# ATTinyServo_v10.net
KiCad netlist of a schematic drawn in EAGLE
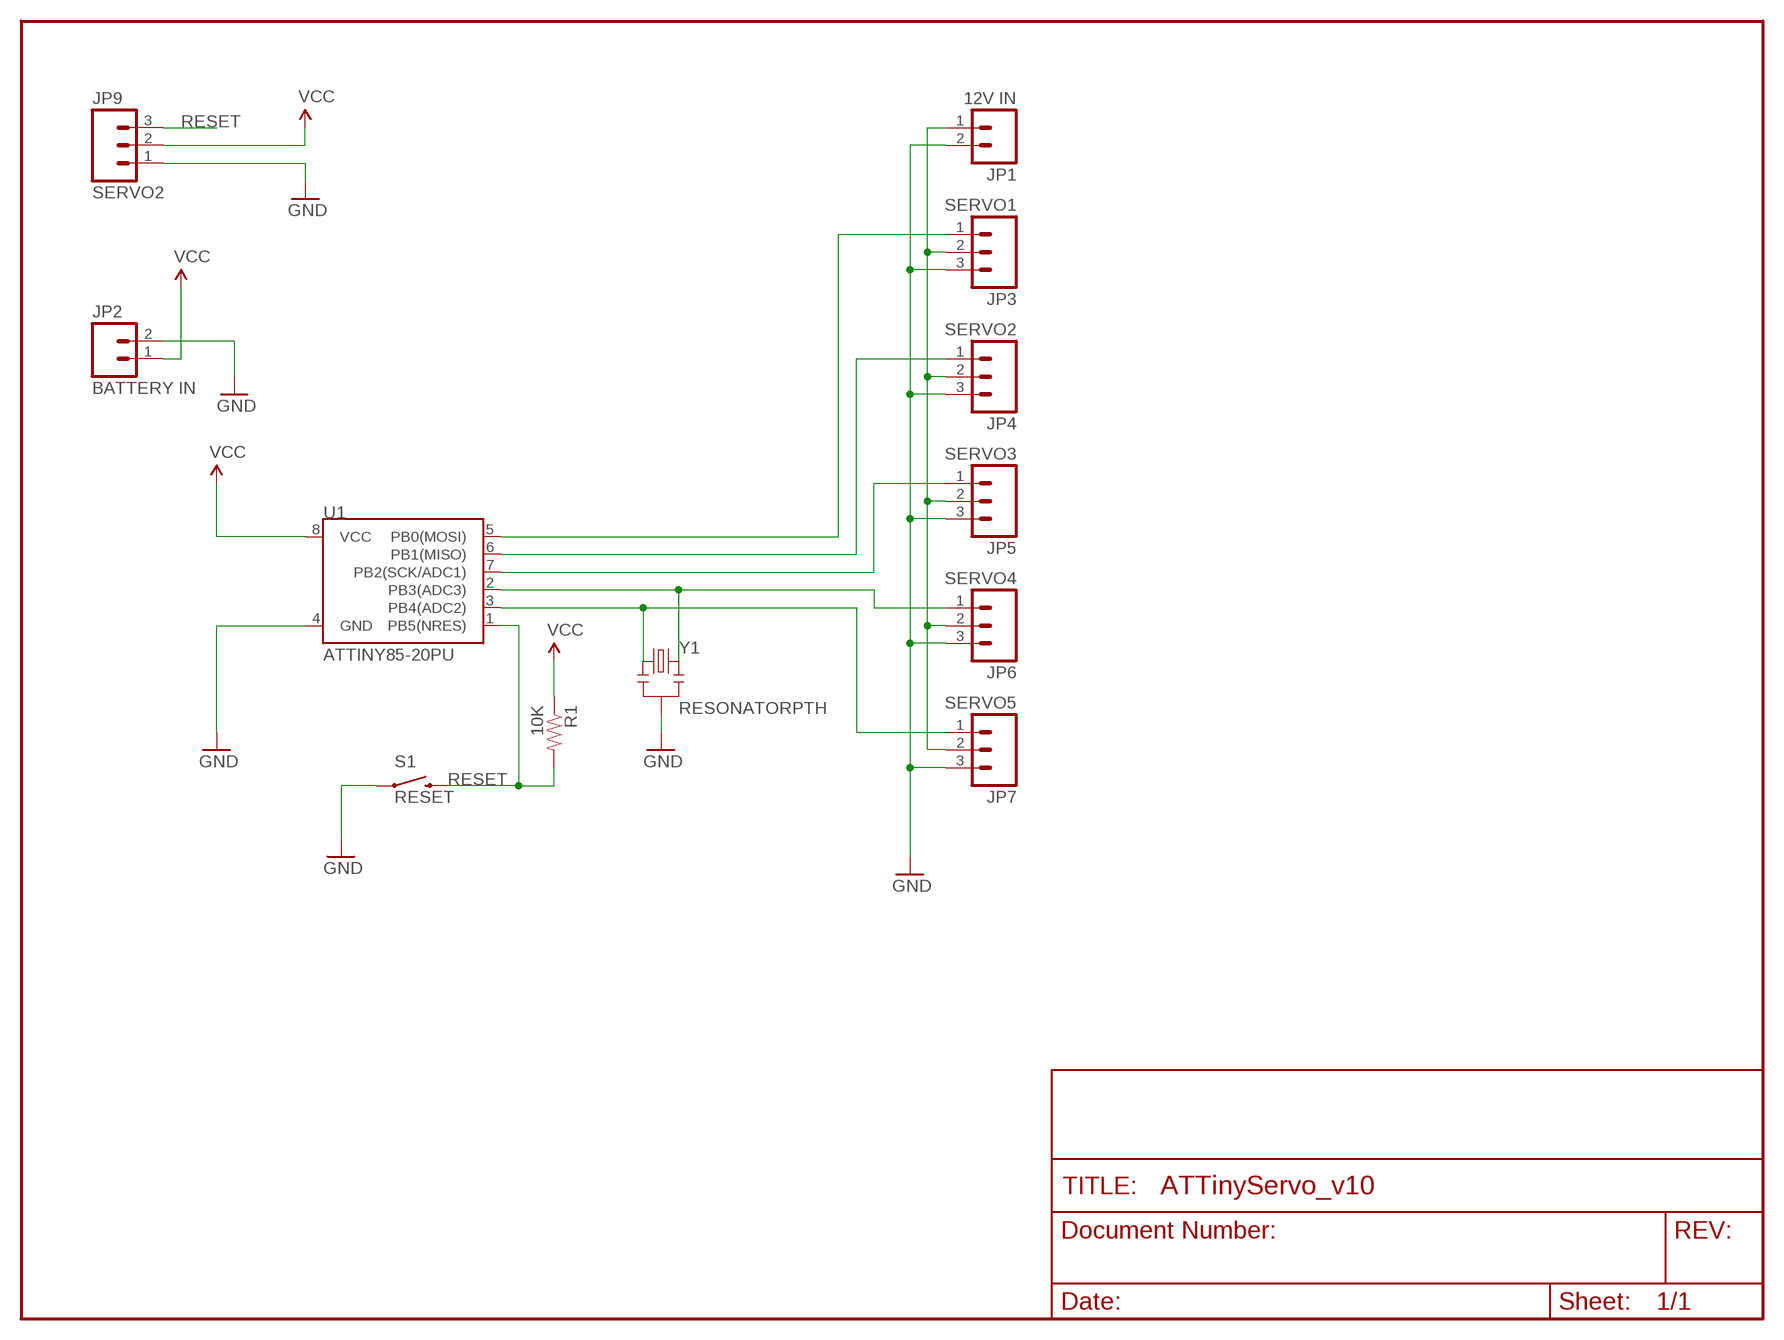
[diagram p0: schematic, sheet 1]

(export (version "E")
  (design (tool "Eeschema 10.0.6"))
  (components
    (comp (ref "JP1")
      (value "12V IN")
      (footprint "eagle-import:SCREWTERMINAL-3.5MM-2")
      (libsource (lib "eagle-import") (part "M023.5MM"))
    )
    (comp (ref "JP2")
      (value "BATTERY IN")
      (footprint "eagle-import:SCREWTERMINAL-3.5MM-2")
      (libsource (lib "eagle-import") (part "M023.5MM"))
    )
    (comp (ref "JP3")
      (value "SERVO1")
      (footprint "eagle-import:1X03")
      (libsource (lib "eagle-import") (part "M03PTH"))
    )
    (comp (ref "JP4")
      (value "SERVO2")
      (footprint "eagle-import:1X03")
      (libsource (lib "eagle-import") (part "M03PTH"))
    )
    (comp (ref "JP5")
      (value "SERVO3")
      (footprint "eagle-import:1X03")
      (libsource (lib "eagle-import") (part "M03PTH"))
    )
    (comp (ref "JP6")
      (value "SERVO4")
      (footprint "eagle-import:1X03")
      (libsource (lib "eagle-import") (part "M03PTH"))
    )
    (comp (ref "JP7")
      (value "SERVO5")
      (footprint "eagle-import:1X03")
      (libsource (lib "eagle-import") (part "M03PTH"))
    )
    (comp (ref "JP9")
      (value "SERVO2")
      (footprint "eagle-import:1X03")
      (libsource (lib "eagle-import") (part "M03PTH"))
    )
    (comp (ref "R1")
      (value "10K")
      (footprint "eagle-import:AXIAL-0.4")
      (libsource (lib "eagle-import") (part "RESISTORPTH-1/4W"))
    )
    (comp (ref "S1")
      (value "RESET")
      (footprint "eagle-import:TACTILE-PTH")
      (libsource (lib "eagle-import") (part "SWITCH-MOMENTARY-2PTH"))
    )
    (comp (ref "U1")
      (value "ATTINY85-20PU")
      (footprint "eagle-import:DIP08")
      (libsource (lib "eagle-import") (part "ATTINY45DIP8"))
    )
    (comp (ref "Y1")
      (value "RESONATORPTH")
      (footprint "eagle-import:RESONATOR-PTH")
      (libsource (lib "eagle-import") (part "RESONATORPTH"))
    )
  )
  (nets
    (net (code "1") (name "/RESET") (class "Default")
      (node (ref "JP9") (pin "3") (pinfunction "3_3") (pintype "passive"))
      (node (ref "R1") (pin "P$2") (pinfunction "2_P$2") (pintype "passive"))
      (node (ref "S1") (pin "3") (pinfunction "2_3") (pintype "passive"))
      (node (ref "U1") (pin "1") (pinfunction "PB5(NRES)_1") (pintype "bidirectional"))
    )
    (net (code "2") (name "GND") (class "Default")
      (node (ref "JP1") (pin "2") (pinfunction "2_2") (pintype "passive"))
      (node (ref "JP2") (pin "2") (pinfunction "2_2") (pintype "passive"))
      (node (ref "JP3") (pin "3") (pinfunction "3_3") (pintype "passive"))
      (node (ref "JP4") (pin "3") (pinfunction "3_3") (pintype "passive"))
      (node (ref "JP5") (pin "3") (pinfunction "3_3") (pintype "passive"))
      (node (ref "JP6") (pin "3") (pinfunction "3_3") (pintype "passive"))
      (node (ref "JP7") (pin "3") (pinfunction "3_3") (pintype "passive"))
      (node (ref "JP9") (pin "1") (pinfunction "1_1") (pintype "passive"))
      (node (ref "S1") (pin "1") (pinfunction "1_1") (pintype "passive"))
      (node (ref "U1") (pin "4") (pinfunction "GND_4") (pintype "bidirectional"))
      (node (ref "Y1") (pin "2") (pinfunction "2_2") (pintype "passive"))
    )
    (net (code "3") (name "Net-(JP1-Pad1)") (class "Default")
      (node (ref "JP1") (pin "1") (pinfunction "1_1") (pintype "passive"))
      (node (ref "JP3") (pin "2") (pinfunction "2_2") (pintype "passive"))
      (node (ref "JP4") (pin "2") (pinfunction "2_2") (pintype "passive"))
      (node (ref "JP5") (pin "2") (pinfunction "2_2") (pintype "passive"))
      (node (ref "JP6") (pin "2") (pinfunction "2_2") (pintype "passive"))
      (node (ref "JP7") (pin "2") (pinfunction "2_2") (pintype "passive"))
    )
    (net (code "4") (name "Net-(U1-PB0(MOSI))") (class "Default")
      (node (ref "JP3") (pin "1") (pinfunction "1_1") (pintype "passive"))
      (node (ref "U1") (pin "5") (pinfunction "PB0(MOSI)_5") (pintype "bidirectional"))
    )
    (net (code "5") (name "Net-(U1-PB1(MISO))") (class "Default")
      (node (ref "JP4") (pin "1") (pinfunction "1_1") (pintype "passive"))
      (node (ref "U1") (pin "6") (pinfunction "PB1(MISO)_6") (pintype "bidirectional"))
    )
    (net (code "6") (name "Net-(U1-PB2(SCK{slash}ADC1))") (class "Default")
      (node (ref "JP5") (pin "1") (pinfunction "1_1") (pintype "passive"))
      (node (ref "U1") (pin "7") (pinfunction "PB2(SCK/ADC1)_7") (pintype "bidirectional"))
    )
    (net (code "7") (name "Net-(U1-PB3(ADC3))") (class "Default")
      (node (ref "JP6") (pin "1") (pinfunction "1_1") (pintype "passive"))
      (node (ref "U1") (pin "2") (pinfunction "PB3(ADC3)_2") (pintype "bidirectional"))
      (node (ref "Y1") (pin "3") (pinfunction "3_3") (pintype "passive"))
    )
    (net (code "8") (name "Net-(U1-PB4(ADC2))") (class "Default")
      (node (ref "JP7") (pin "1") (pinfunction "1_1") (pintype "passive"))
      (node (ref "U1") (pin "3") (pinfunction "PB4(ADC2)_3") (pintype "bidirectional"))
      (node (ref "Y1") (pin "1") (pinfunction "1_1") (pintype "passive"))
    )
    (net (code "9") (name "VCC") (class "Default")
      (node (ref "JP2") (pin "1") (pinfunction "1_1") (pintype "passive"))
      (node (ref "JP9") (pin "2") (pinfunction "2_2") (pintype "passive"))
      (node (ref "R1") (pin "P$1") (pinfunction "1_P$1") (pintype "passive"))
      (node (ref "U1") (pin "8") (pinfunction "VCC_8") (pintype "bidirectional"))
    )
  )
)
